# RefPoint01-00.net
KiCad netlist of a schematic drawn in Altium Designer
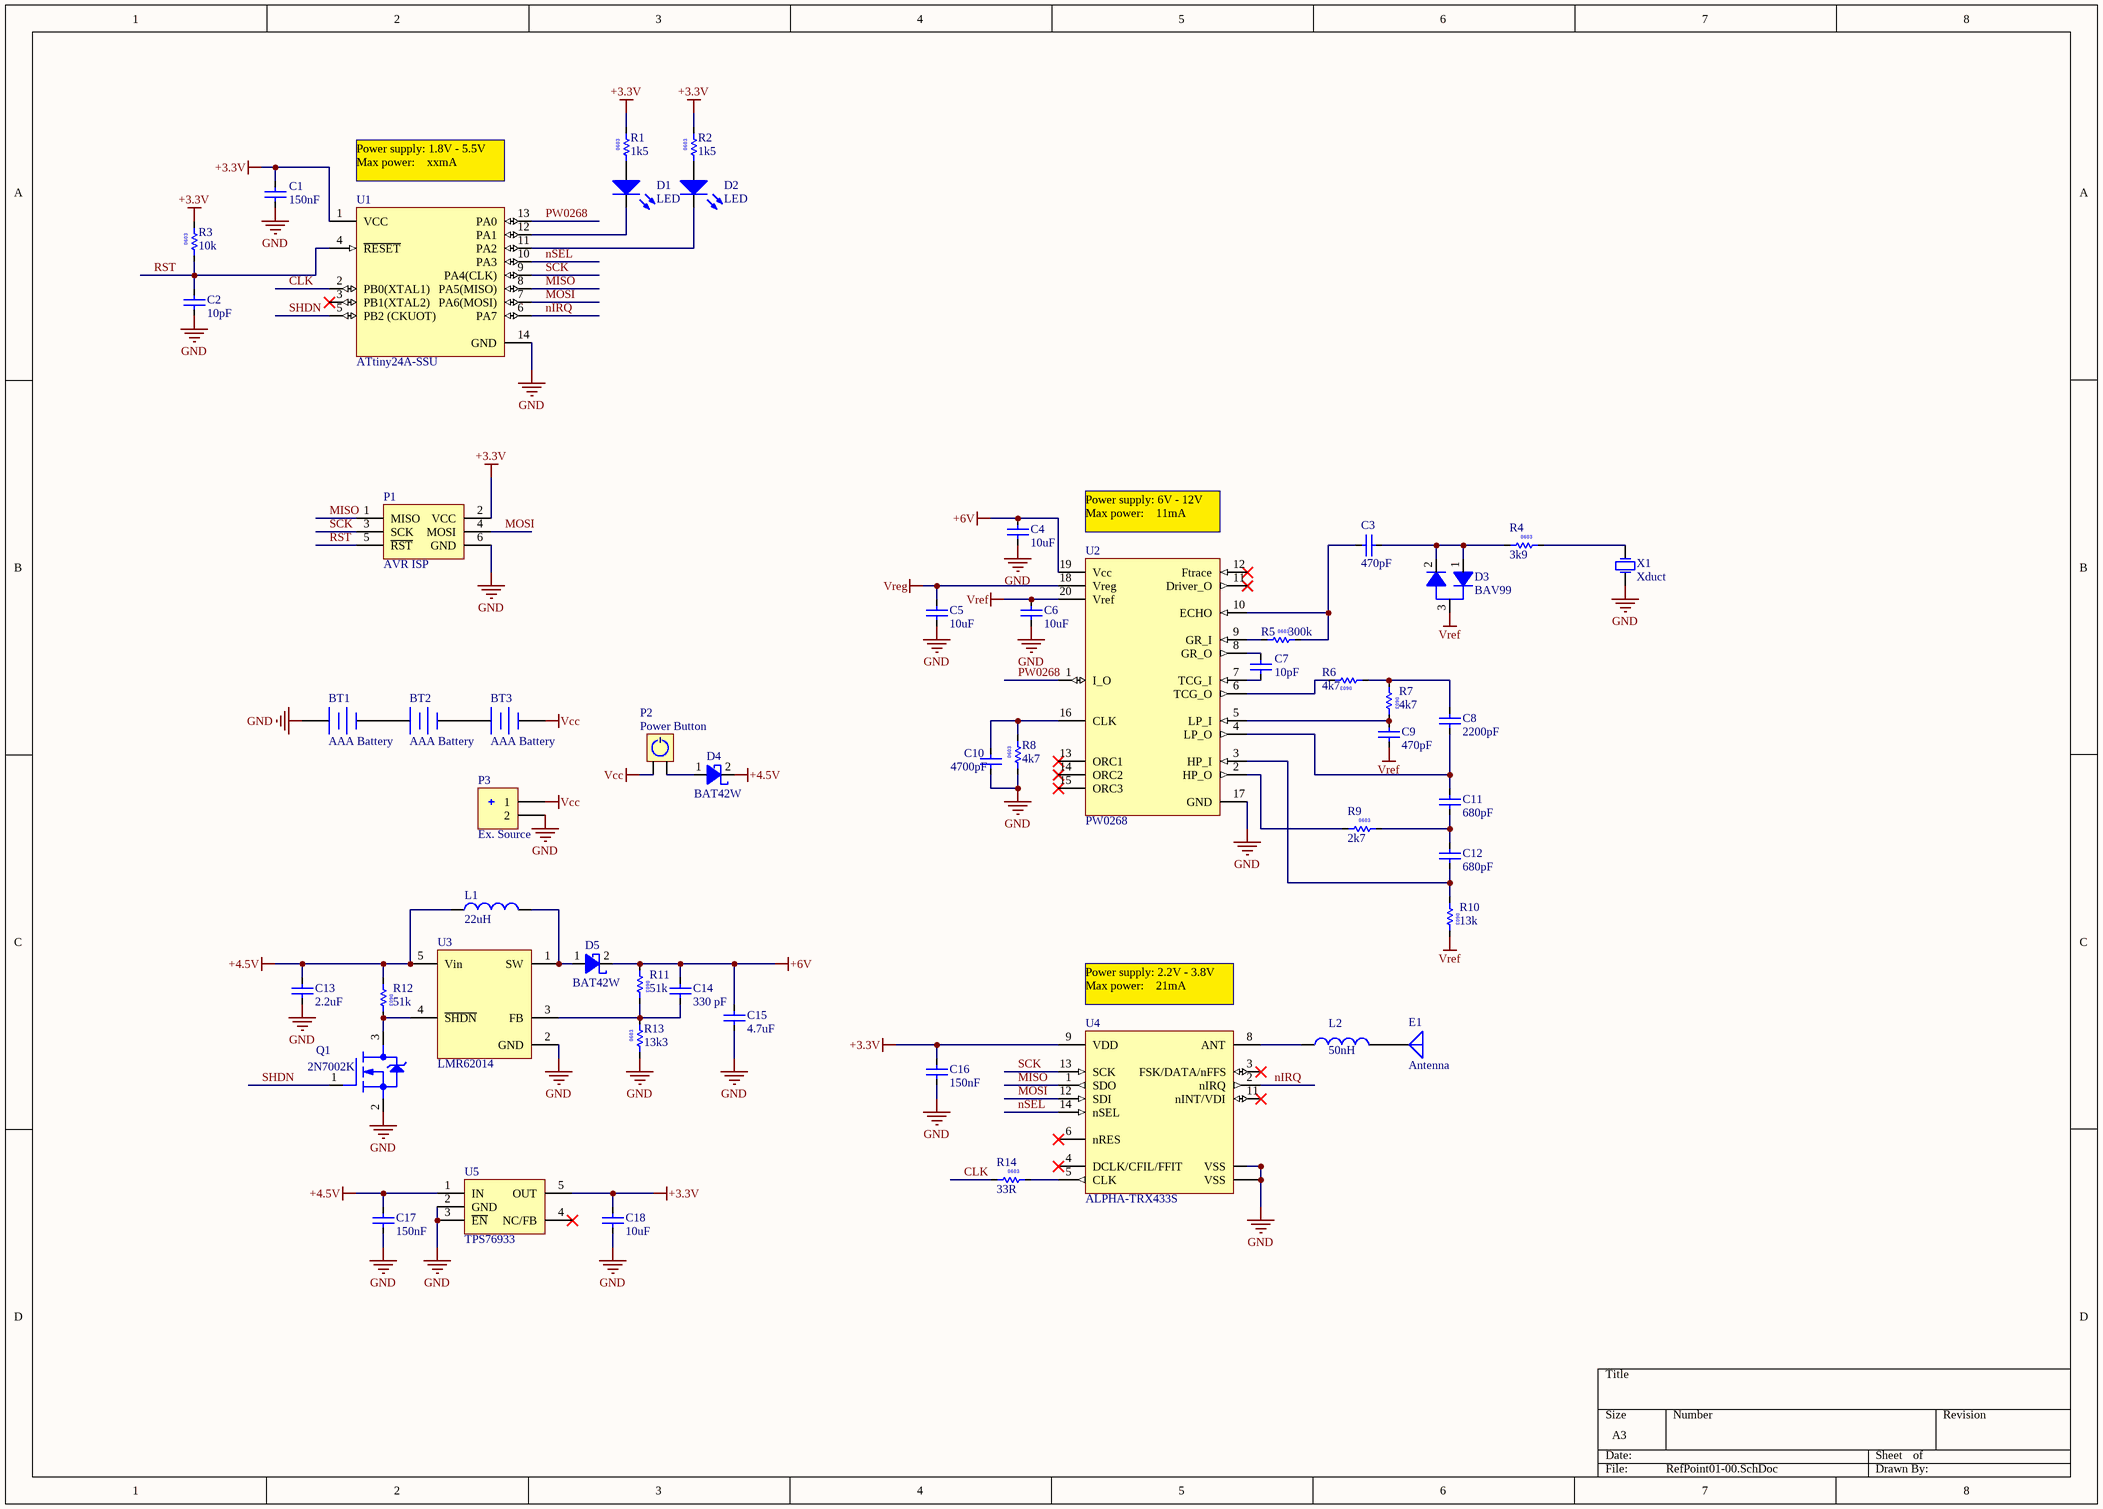
[diagram p0: RefPoint01-00.SchDoc]

(export (version "E")
  (design (tool "Eeschema 10.0.6"))
  (components
    (comp (ref "BT1")
      (value "AAA Battery")
      (footprint "Keystone 55 AAA CLIP")
      (description "Battery AAA")
      (fields (field (name "MANUFACTURER") "KEYSTONE") (field (name "MANUFACTURER PART NUMBER") "55"))
      (libsource (lib "UserSchlib") (part "Battery_AAA"))
    )
    (comp (ref "BT2")
      (value "AAA Battery")
      (footprint "Keystone 55 AAA CLIP")
      (description "Battery AAA")
      (fields (field (name "MANUFACTURER") "KEYSTONE") (field (name "MANUFACTURER PART NUMBER") "55"))
      (libsource (lib "UserSchlib") (part "Battery_AAA"))
    )
    (comp (ref "BT3")
      (value "AAA Battery")
      (footprint "Keystone 55 AAA CLIP")
      (description "Battery AAA")
      (fields (field (name "MANUFACTURER") "KEYSTONE") (field (name "MANUFACTURER PART NUMBER") "55"))
      (libsource (lib "UserSchlib") (part "Battery_AAA"))
    )
    (comp (ref "C1")
      (value "150nF")
      (footprint "CAPC1608N")
      (description "MLCC, 150nF 16V -20+80% Y5V")
      (fields (field (name "PART NUMBER") "C0000001") (field (name "VOLTAGE") "16"))
      (libsource (lib "KTU_DB") (part "C_SM"))
    )
    (comp (ref "C2")
      (value "10pF")
      (footprint "CAPC1608N")
      (description "MLCC, 0603, NP0, 50V, 10PF")
      (fields (field (name "PART NUMBER") "C0000042") (field (name "VOLTAGE") "100"))
      (libsource (lib "KTU_DB") (part "C_SM"))
    )
    (comp (ref "C3")
      (value "470pF")
      (footprint "CAPC1608N")
      (description "MLCC, 470pF 50V C0G 5% 0603")
      (fields (field (name "PART NUMBER") "C0000062") (field (name "VOLTAGE") "50"))
      (libsource (lib "KTU_DB") (part "C_SM"))
    )
    (comp (ref "C4")
      (value "10uF")
      (footprint "CAPC3216N")
      (description "MLCC, 10uF 25V -20%, +80% Y5V 1206")
      (fields (field (name "PART NUMBER") "C0000011") (field (name "VOLTAGE") "25"))
      (libsource (lib "KTU_DB") (part "C_SM"))
    )
    (comp (ref "C5")
      (value "10uF")
      (footprint "CAPC3216N")
      (description "MLCC, 10uF 25V -20%, +80% Y5V 1206")
      (fields (field (name "PART NUMBER") "C0000011") (field (name "VOLTAGE") "25"))
      (libsource (lib "KTU_DB") (part "C_SM"))
    )
    (comp (ref "C6")
      (value "10uF")
      (footprint "CAPC3216N")
      (description "MLCC, 10uF 25V -20%, +80% Y5V 1206")
      (fields (field (name "PART NUMBER") "C0000011") (field (name "VOLTAGE") "25"))
      (libsource (lib "KTU_DB") (part "C_SM"))
    )
    (comp (ref "C7")
      (value "10pF")
      (footprint "CAPC1608N")
      (description "MLCC, 0603, NP0, 50V, 10PF")
      (fields (field (name "PART NUMBER") "C0000042") (field (name "VOLTAGE") "100"))
      (libsource (lib "KTU_DB") (part "C_SM"))
    )
    (comp (ref "C8")
      (value "2200pF")
      (footprint "CAPC1608N")
      (description "MLCC, 2200pF 50V X7R 5% 0603")
      (fields (field (name "PART NUMBER") "C0000126") (field (name "VOLTAGE") "50"))
      (libsource (lib "KTU_DB") (part "C_SM"))
    )
    (comp (ref "C9")
      (value "470pF")
      (footprint "CAPC1608N")
      (description "MLCC, 470pF 50V C0G 5% 0603")
      (fields (field (name "PART NUMBER") "C0000062") (field (name "VOLTAGE") "50"))
      (libsource (lib "KTU_DB") (part "C_SM"))
    )
    (comp (ref "C10")
      (value "4700pF")
      (footprint "CAPC1608N")
      (description "MLCC, 4700pF 50V X7R 5% 0603")
      (fields (field (name "PART NUMBER") "C0000127") (field (name "VOLTAGE") "50"))
      (libsource (lib "KTU_DB") (part "C_SM"))
    )
    (comp (ref "C11")
      (value "680pF")
      (footprint "CAPC1608N")
      (description "MLCC, 680pF 50V C0G / NP0 5% 0603")
      (fields (field (name "PART NUMBER") "C0000125") (field (name "VOLTAGE") "50"))
      (libsource (lib "KTU_DB") (part "C_SM"))
    )
    (comp (ref "C12")
      (value "680pF")
      (footprint "CAPC1608N")
      (description "MLCC, 680pF 50V C0G / NP0 5% 0603")
      (fields (field (name "PART NUMBER") "C0000125") (field (name "VOLTAGE") "50"))
      (libsource (lib "KTU_DB") (part "C_SM"))
    )
    (comp (ref "C13")
      (value "2.2uF")
      (footprint "CAPC2012N")
      (description "MLCC, 2.2uF 16V X7R 0805")
      (fields (field (name "PART NUMBER") "C0000129") (field (name "VOLTAGE") "16V"))
      (libsource (lib "KTU_DB") (part "C_SM"))
    )
    (comp (ref "C14")
      (value "330 pF")
      (footprint "CAPC1608N")
      (description "MLCC, 50V, 330pF, 10%, X7R, 0603")
      (fields (field (name "PART NUMBER") "C0000018") (field (name "VOLTAGE") "50"))
      (libsource (lib "KTU_DB") (part "C_SM"))
    )
    (comp (ref "C15")
      (value "4.7uF")
      (footprint "CAPC3225N")
      (description "MLCC, 4.7uF 16V X7R 1210")
      (fields (field (name "PART NUMBER") "C0000130") (field (name "VOLTAGE") "50V"))
      (libsource (lib "KTU_DB") (part "C_SM"))
    )
    (comp (ref "C16")
      (value "150nF")
      (footprint "CAPC1608N")
      (description "MLCC, 150nF 16V -20+80% Y5V")
      (fields (field (name "PART NUMBER") "C0000001") (field (name "VOLTAGE") "16"))
      (libsource (lib "KTU_DB") (part "C_SM"))
    )
    (comp (ref "C17")
      (value "150nF")
      (footprint "CAPC1608N")
      (description "MLCC, 150nF 16V -20+80% Y5V")
      (fields (field (name "PART NUMBER") "C0000001") (field (name "VOLTAGE") "16"))
      (libsource (lib "KTU_DB") (part "C_SM"))
    )
    (comp (ref "C18")
      (value "10uF")
      (footprint "CAPC3216N")
      (description "MLCC, 10uF 25V -20%, +80% Y5V 1206")
      (fields (field (name "PART NUMBER") "C0000011") (field (name "VOLTAGE") "25"))
      (libsource (lib "KTU_DB") (part "C_SM"))
    )
    (comp (ref "D1")
      (value "LED")
      (footprint "LED 3mm DIP")
      (description "Typical INFRARED GaAs LED")
      (fields (field (name "PUBLISHER") "Altium Limited"))
      (libsource (lib "UserSchlib") (part "LED0"))
    )
    (comp (ref "D2")
      (value "LED")
      (footprint "LED 3mm DIP")
      (description "Typical INFRARED GaAs LED")
      (fields (field (name "PUBLISHER") "Altium Limited"))
      (libsource (lib "UserSchlib") (part "LED0"))
    )
    (comp (ref "D3")
      (value "BAV99")
      (footprint "SOT95P240-3L")
      (description "DIODE SW DUAL 75V 350mW SOT23")
      (fields (field (name "PART NUMBER") "D0000001") (field (name "MANUFACTURER") "ON SEMICONDUCTOR"))
      (libsource (lib "KTU_DB") (part "BAV99"))
    )
    (comp (ref "D4")
      (value "BAT42W")
      (footprint "SOD123")
      (description "Diode Schottkey, 30V, Vf=1V, If=1A, rrt=5ns, SOD123, -55°C to +125°C")
      (fields (field (name "PART NUMBER") "D0000003") (field (name "MANUFACTURER") "VISHAY SEMICONDUCTOR"))
      (libsource (lib "KTU_DB") (part "Diode_SCHOTTKY"))
    )
    (comp (ref "D5")
      (value "BAT42W")
      (footprint "SOD123")
      (description "Diode Schottkey, 30V, Vf=1V, If=1A, rrt=5ns, SOD123, -55°C to +125°C")
      (fields (field (name "PART NUMBER") "D0000003") (field (name "MANUFACTURER") "VISHAY SEMICONDUCTOR"))
      (libsource (lib "KTU_DB") (part "Diode_SCHOTTKY"))
    )
    (comp (ref "E1")
      (value "Antenna")
      (description "Generic Antenna")
      (fields (field (name "PUBLISHER") "Altium Limited"))
      (libsource (lib "Miscellaneous Devices") (part "Antenna"))
    )
    (comp (ref "L1")
      (value "22uH")
      (footprint "INDM7070x32N")
      (description "Inductor")
      (fields
        (field (name "MANUFACTURER PART NUMBER") "810-SLF732220MR962PF")
        (field (name "MANUFACTURER") "TDK")
      )
      (libsource (lib "UserSchlib") (part "L Inductor 810-SLF732220MR962PF"))
    )
    (comp (ref "L2")
      (value "50nH")
      (footprint "INDC2012L")
      (description "Inductor")
      (fields (field (name "PUBLISHER") "Altium Limited"))
      (libsource (lib "Miscellaneous Devices") (part "Inductor"))
    )
    (comp (ref "P1")
      (value "AVR ISP")
      (footprint "HDR2X3")
      (description "Header, 6-Pin")
      (fields (field (name "PUBLISHER") "Altium Limited"))
      (libsource (lib "Arthur Shematic") (part "AVR ISP"))
    )
    (comp (ref "P2")
      (value "Power Button")
      (footprint "HDR1X2")
      (description "Header, 2-Pin, Right Angle")
      (fields (field (name "PUBLISHER") "Altium Limited"))
      (libsource (lib "UserSchlib") (part "Power Button"))
    )
    (comp (ref "P3")
      (value "Ex. Source")
      (footprint "HDR1X2")
      (description "Header, 2-Pin")
      (fields (field (name "PUBLISHER") "Altium Limited"))
      (libsource (lib "Arthur Shematic") (part "Maitinimas"))
    )
    (comp (ref "Q1")
      (value "2N7002K")
      (footprint "SOT23-3L")
      (description "MOSFET N-CH 60V 340MA SOT23")
      (fields (field (name "PART NUMBER") "Q0000008") (field (name "MANUFACTURER") "NXP"))
      (libsource (lib "KTU_DB") (part "MOSFET_N_GSD"))
    )
    (comp (ref "R1")
      (value "1k5")
      (footprint "RESC1608N")
      (description "1K5 5% 0603 1/10W")
      (fields (field (name "TOLERANCE") "±5%") (field (name "POWER") "1/10W"))
      (libsource (lib "KTU_DB") (part "R0603"))
    )
    (comp (ref "R2")
      (value "1k5")
      (footprint "RESC1608N")
      (description "1K5 5% 0603 1/10W")
      (fields (field (name "TOLERANCE") "±5%") (field (name "POWER") "1/10W"))
      (libsource (lib "KTU_DB") (part "R0603"))
    )
    (comp (ref "R3")
      (value "10k")
      (footprint "RESC1608N")
      (description "Res, 10K 0.063W 75V 1%  0603")
      (fields (field (name "TOLERANCE") "±1%") (field (name "POWER") "0.063W"))
      (libsource (lib "KTU_DB") (part "R0603"))
    )
    (comp (ref "R4")
      (value "3k9")
      (footprint "RESC1608N")
      (description "3K9 5% 0603 1/10W")
      (fields (field (name "TOLERANCE") "±5%") (field (name "POWER") "1/10W"))
      (libsource (lib "KTU_DB") (part "R0603"))
    )
    (comp (ref "R5")
      (value "300k")
      (footprint "RESC1608N")
      (description "300K 5% 0603 1/10W")
      (fields (field (name "TOLERANCE") "±5%") (field (name "POWER") "1/10W"))
      (libsource (lib "KTU_DB") (part "R0603"))
    )
    (comp (ref "R6")
      (value "4k7")
      (footprint "RESC1608N")
      (description "Res, 4K7 5% 0603 1/10W")
      (fields (field (name "TOLERANCE") "±5%") (field (name "POWER") "1/10W"))
      (libsource (lib "KTU_DB") (part "R0603"))
    )
    (comp (ref "R7")
      (value "4k7")
      (footprint "RESC1608N")
      (description "Res, 4K7 5% 0603 1/10W")
      (fields (field (name "TOLERANCE") "±5%") (field (name "POWER") "1/10W"))
      (libsource (lib "KTU_DB") (part "R0603"))
    )
    (comp (ref "R8")
      (value "4k7")
      (footprint "RESC1608N")
      (description "Res, 4K7 5% 0603 1/10W")
      (fields (field (name "TOLERANCE") "±5%") (field (name "POWER") "1/10W"))
      (libsource (lib "KTU_DB") (part "R0603"))
    )
    (comp (ref "R9")
      (value "2k7")
      (footprint "RESC1608N")
      (description "2K7 5% 0603 1/10W")
      (fields (field (name "TOLERANCE") "±5%") (field (name "POWER") "1/10W"))
      (libsource (lib "KTU_DB") (part "R0603"))
    )
    (comp (ref "R10")
      (value "13k")
      (footprint "RESC1608N")
      (description "13K 5% 0603 1/10W")
      (fields (field (name "TOLERANCE") "±5%") (field (name "POWER") "1/10W"))
      (libsource (lib "KTU_DB") (part "R0603"))
    )
    (comp (ref "R11")
      (value "51k")
      (footprint "RESC1608X50N")
      (description "Res, 51K, 0603 (1608 metric), ±1%, 100mW, 75V")
      (fields (field (name "TOLERANCE") "±1%") (field (name "POWER") "100mW"))
      (libsource (lib "KTU_DB") (part "R0603"))
    )
    (comp (ref "R12")
      (value "51k")
      (footprint "RESC1608X50N")
      (description "Res, 51K, 0603 (1608 metric), ±1%, 100mW, 75V")
      (fields (field (name "TOLERANCE") "±1%") (field (name "POWER") "100mW"))
      (libsource (lib "KTU_DB") (part "R0603"))
    )
    (comp (ref "R13")
      (value "13k3")
      (footprint "RESC1608X50N")
      (description "Res, 13K3, 0603 (1608 metric), ±1%, 100mW, 75V")
      (fields (field (name "TOLERANCE") "±1%") (field (name "POWER") "100mW"))
      (libsource (lib "KTU_DB") (part "R0603"))
    )
    (comp (ref "R14")
      (value "33R")
      (footprint "RESC1608N")
      (description "33R 5% 0603 1/10W")
      (fields (field (name "TOLERANCE") "±5%") (field (name "POWER") "1/10W"))
      (libsource (lib "KTU_DB") (part "R0603"))
    )
    (comp (ref "U1")
      (value "ATtiny24A-SSU")
      (footprint "UserPcbLib:SOIC14T_L")
      (fields (field (name "MANUFACTURER") "Atmel"))
      (libsource (lib "UserSchlib") (part "ATtiny24A-SSU"))
    )
    (comp (ref "U2")
      (value "PW0268")
      (footprint "QSSOP20_0.635/4.0X8.7")
      (fields (field (name "MANUFACTURER") "PROWAVE"))
      (libsource (lib "UserSchlib") (part "PW0268"))
    )
    (comp (ref "U3")
      (value "LMR62014")
      (footprint "SOT23-5AM")
      (description "2064695")
      (fields
        (field (name "MANUFACTURER PART NUMBER") "LMR62014XMFE")
        (field (name "MANUFACTURER") "TEXAS INSTRUMENTS")
      )
      (libsource (lib "UserSchlib") (part "LMR62014"))
    )
    (comp (ref "U4")
      (value "ALPHA-TRX433S")
      (footprint "ALPHA-TRX")
      (description "RF SOLUTIONS  ALPHA-TRX433S  RF MODULE, TRANSCEIVER, FSK, 433MHZ")
      (fields (field (name "MANUFACTURER") "RF SOLUTIONS"))
      (libsource (lib "UserSchlib") (part "ALPHA-TRX433S"))
    )
    (comp (ref "U5")
      (value "TPS76933")
      (footprint "SOT23-5AM")
      (description "ULTRALOW-POWER 100-mA LOW-DROPOUT LINEAR REGULATORS")
      (fields
        (field (name "MANUFACTURER PART NUMBER") "TPS76933DBVT")
        (field (name "MANUFACTURER") "TEXAS INSTRUMENTS")
      )
      (libsource (lib "UserSchlib") (part "TPS769xx"))
    )
    (comp (ref "X1")
      (value "Xduct")
      (footprint "Xducts1")
      (description "Transducer")
      (libsource (lib "UserSchlib") (part "Xduct1"))
    )
  )
  (nets
    (net (code "1") (name "+3.3V") (class "Default")
      (node (ref "C1") (pin "2") (pinfunction "2_2") (pintype "passive"))
      (node (ref "C16") (pin "2") (pinfunction "2_2") (pintype "passive"))
      (node (ref "C18") (pin "2") (pinfunction "2_2") (pintype "passive"))
      (node (ref "P1") (pin "2") (pinfunction "VCC_2") (pintype "passive"))
      (node (ref "R1") (pin "2") (pinfunction "2_2") (pintype "passive"))
      (node (ref "R2") (pin "2") (pinfunction "2_2") (pintype "passive"))
      (node (ref "R3") (pin "2") (pinfunction "2_2") (pintype "passive"))
      (node (ref "U1") (pin "1") (pinfunction "VCC_1") (pintype "power_in"))
      (node (ref "U4") (pin "9") (pinfunction "VDD_9") (pintype "power_in"))
      (node (ref "U5") (pin "5") (pinfunction "OUT_5") (pintype "power_in"))
    )
    (net (code "2") (name "+4.5V") (class "Default")
      (node (ref "C13") (pin "2") (pinfunction "2_2") (pintype "passive"))
      (node (ref "C17") (pin "2") (pinfunction "2_2") (pintype "passive"))
      (node (ref "D4") (pin "2") (pinfunction "CATHODE_2") (pintype "passive"))
      (node (ref "L1") (pin "2") (pinfunction "2_2") (pintype "passive"))
      (node (ref "R12") (pin "1") (pinfunction "1_1") (pintype "passive"))
      (node (ref "U3") (pin "5") (pinfunction "Vin_5") (pintype "passive"))
      (node (ref "U5") (pin "1") (pinfunction "IN_1") (pintype "power_in"))
    )
    (net (code "3") (name "+6V") (class "Default")
      (node (ref "C14") (pin "2") (pinfunction "2_2") (pintype "passive"))
      (node (ref "C15") (pin "2") (pinfunction "2_2") (pintype "passive"))
      (node (ref "C4") (pin "2") (pinfunction "2_2") (pintype "passive"))
      (node (ref "D5") (pin "2") (pinfunction "CATHODE_2") (pintype "passive"))
      (node (ref "R11") (pin "1") (pinfunction "1_1") (pintype "passive"))
      (node (ref "U2") (pin "19") (pinfunction "Vcc_19") (pintype "power_in"))
    )
    (net (code "4") (name "/CLK") (class "Default")
      (node (ref "R14") (pin "1") (pinfunction "1_1") (pintype "passive"))
      (node (ref "U1") (pin "2") (pinfunction "PB0(XTAL1)_2") (pintype "bidirectional"))
    )
    (net (code "5") (name "/MISO") (class "Default")
      (node (ref "P1") (pin "1") (pinfunction "MISO_1") (pintype "passive"))
      (node (ref "U1") (pin "8") (pinfunction "PA5(MISO)_8") (pintype "bidirectional"))
      (node (ref "U4") (pin "1") (pinfunction "SDO_1") (pintype "output"))
    )
    (net (code "6") (name "/MOSI") (class "Default")
      (node (ref "P1") (pin "4") (pinfunction "MOSI_4") (pintype "passive"))
      (node (ref "U1") (pin "7") (pinfunction "PA6(MOSI)_7") (pintype "bidirectional"))
      (node (ref "U4") (pin "12") (pinfunction "SDI_12") (pintype "input"))
    )
    (net (code "7") (name "/PW0268") (class "Default")
      (node (ref "U1") (pin "13") (pinfunction "PA0_13") (pintype "bidirectional"))
      (node (ref "U2") (pin "1") (pinfunction "I_O_1") (pintype "bidirectional"))
    )
    (net (code "8") (name "/RST") (class "Default")
      (node (ref "C2") (pin "2") (pinfunction "2_2") (pintype "passive"))
      (node (ref "P1") (pin "5") (pinfunction "~{RST}_5") (pintype "passive"))
      (node (ref "R3") (pin "1") (pinfunction "1_1") (pintype "passive"))
      (node (ref "U1") (pin "4") (pinfunction "~{RESET}_4") (pintype "input"))
    )
    (net (code "9") (name "/SCK") (class "Default")
      (node (ref "P1") (pin "3") (pinfunction "SCK_3") (pintype "passive"))
      (node (ref "U1") (pin "9") (pinfunction "PA4(CLK)_9") (pintype "bidirectional"))
      (node (ref "U4") (pin "13") (pinfunction "SCK_13") (pintype "input"))
    )
    (net (code "10") (name "/SHDN") (class "Default")
      (node (ref "Q1") (pin "1") (pinfunction "G_1") (pintype "passive"))
      (node (ref "U1") (pin "5") (pinfunction "PB2_(CKUOT)_5") (pintype "bidirectional"))
    )
    (net (code "11") (name "/nIRQ") (class "Default")
      (node (ref "U1") (pin "6") (pinfunction "PA7_6") (pintype "bidirectional"))
      (node (ref "U4") (pin "2") (pinfunction "nIRQ_2") (pintype "output"))
    )
    (net (code "12") (name "/nSEL") (class "Default")
      (node (ref "U1") (pin "10") (pinfunction "PA3_10") (pintype "bidirectional"))
      (node (ref "U4") (pin "14") (pinfunction "nSEL_14") (pintype "input"))
    )
    (net (code "13") (name "GND") (class "Default")
      (node (ref "BT1") (pin "1") (pinfunction "+_1") (pintype "passive"))
      (node (ref "C1") (pin "1") (pinfunction "1_1") (pintype "passive"))
      (node (ref "C10") (pin "1") (pinfunction "1_1") (pintype "passive"))
      (node (ref "C13") (pin "1") (pinfunction "1_1") (pintype "passive"))
      (node (ref "C15") (pin "1") (pinfunction "1_1") (pintype "passive"))
      (node (ref "C16") (pin "1") (pinfunction "1_1") (pintype "passive"))
      (node (ref "C17") (pin "1") (pinfunction "1_1") (pintype "passive"))
      (node (ref "C18") (pin "1") (pinfunction "1_1") (pintype "passive"))
      (node (ref "C2") (pin "1") (pinfunction "1_1") (pintype "passive"))
      (node (ref "C4") (pin "1") (pinfunction "1_1") (pintype "passive"))
      (node (ref "C5") (pin "1") (pinfunction "1_1") (pintype "passive"))
      (node (ref "C6") (pin "1") (pinfunction "1_1") (pintype "passive"))
      (node (ref "P1") (pin "6") (pinfunction "GND_6") (pintype "passive"))
      (node (ref "P3") (pin "2") (pinfunction "2_2") (pintype "passive"))
      (node (ref "Q1") (pin "2") (pinfunction "S_2") (pintype "passive"))
      (node (ref "R13") (pin "1") (pinfunction "1_1") (pintype "passive"))
      (node (ref "R8") (pin "1") (pinfunction "1_1") (pintype "passive"))
      (node (ref "U1") (pin "14") (pinfunction "GND_14") (pintype "power_in"))
      (node (ref "U2") (pin "17") (pinfunction "GND_17") (pintype "power_in"))
      (node (ref "U3") (pin "2") (pinfunction "GND_2") (pintype "passive"))
      (node (ref "U4") (pin "10") (pinfunction "VSS_10") (pintype "power_in"))
      (node (ref "U4") (pin "7") (pinfunction "VSS_7") (pintype "power_in"))
      (node (ref "U5") (pin "2") (pinfunction "GND_2") (pintype "power_in"))
      (node (ref "U5") (pin "3") (pinfunction "~{EN}_3") (pintype "power_in"))
      (node (ref "X1") (pin "2") (pinfunction "2_2") (pintype "passive"))
    )
    (net (code "14") (name "Net-(BT1--)") (class "Default")
      (node (ref "BT1") (pin "2") (pinfunction "-_2") (pintype "passive"))
      (node (ref "BT2") (pin "1") (pinfunction "+_1") (pintype "passive"))
    )
    (net (code "15") (name "Net-(BT2--)") (class "Default")
      (node (ref "BT2") (pin "2") (pinfunction "-_2") (pintype "passive"))
      (node (ref "BT3") (pin "1") (pinfunction "+_1") (pintype "passive"))
    )
    (net (code "16") (name "Net-(C8-Pad2)") (class "Default")
      (node (ref "C8") (pin "2") (pinfunction "2_2") (pintype "passive"))
      (node (ref "R6") (pin "1") (pinfunction "1_1") (pintype "passive"))
      (node (ref "R7") (pin "1") (pinfunction "1_1") (pintype "passive"))
    )
    (net (code "17") (name "Net-(C11-Pad2)") (class "Default")
      (node (ref "C11") (pin "2") (pinfunction "2_2") (pintype "passive"))
      (node (ref "C12") (pin "1") (pinfunction "1_1") (pintype "passive"))
      (node (ref "R9") (pin "2") (pinfunction "2_2") (pintype "passive"))
    )
    (net (code "18") (name "Net-(D1-A)") (class "Default")
      (node (ref "D1") (pin "1") (pinfunction "A_1") (pintype "passive"))
      (node (ref "R1") (pin "1") (pinfunction "1_1") (pintype "passive"))
    )
    (net (code "19") (name "Net-(D1-K)") (class "Default")
      (node (ref "D1") (pin "2") (pinfunction "K_2") (pintype "passive"))
      (node (ref "U1") (pin "12") (pinfunction "PA1_12") (pintype "bidirectional"))
    )
    (net (code "20") (name "Net-(D2-A)") (class "Default")
      (node (ref "D2") (pin "1") (pinfunction "A_1") (pintype "passive"))
      (node (ref "R2") (pin "1") (pinfunction "1_1") (pintype "passive"))
    )
    (net (code "21") (name "Net-(D2-K)") (class "Default")
      (node (ref "D2") (pin "2") (pinfunction "K_2") (pintype "passive"))
      (node (ref "U1") (pin "11") (pinfunction "PA2_11") (pintype "bidirectional"))
    )
    (net (code "22") (name "Net-(D3-A)") (class "Default")
      (node (ref "C3") (pin "2") (pinfunction "2_2") (pintype "passive"))
      (node (ref "D3") (pin "1") (pinfunction "A1_1") (pintype "passive"))
      (node (ref "D3") (pin "2") (pinfunction "A_2") (pintype "passive"))
      (node (ref "R4") (pin "1") (pinfunction "1_1") (pintype "passive"))
    )
    (net (code "23") (name "Net-(D4-ANODE)") (class "Default")
      (node (ref "D4") (pin "1") (pinfunction "ANODE_1") (pintype "passive"))
      (node (ref "P2") (pin "2") (pinfunction "2_2") (pintype "passive"))
    )
    (net (code "24") (name "Net-(D5-ANODE)") (class "Default")
      (node (ref "D5") (pin "1") (pinfunction "ANODE_1") (pintype "passive"))
      (node (ref "L1") (pin "1") (pinfunction "1_1") (pintype "passive"))
      (node (ref "U3") (pin "1") (pinfunction "SW_1") (pintype "passive"))
    )
    (net (code "25") (name "Net-(E1-A)") (class "Default")
      (node (ref "E1") (pin "1") (pinfunction "A_1") (pintype "passive"))
      (node (ref "L2") (pin "2") (pinfunction "2_2") (pintype "passive"))
    )
    (net (code "26") (name "Net-(Q1-D)") (class "Default")
      (node (ref "Q1") (pin "3") (pinfunction "D_3") (pintype "passive"))
      (node (ref "R12") (pin "2") (pinfunction "2_2") (pintype "passive"))
      (node (ref "U3") (pin "4") (pinfunction "~{SHDN}_4") (pintype "passive"))
    )
    (net (code "27") (name "Net-(R4-Pad2)") (class "Default")
      (node (ref "R4") (pin "2") (pinfunction "2_2") (pintype "passive"))
      (node (ref "X1") (pin "1") (pinfunction "1_1") (pintype "passive"))
    )
    (net (code "28") (name "Net-(U2-CLK)") (class "Default")
      (node (ref "C10") (pin "2") (pinfunction "2_2") (pintype "passive"))
      (node (ref "R8") (pin "2") (pinfunction "2_2") (pintype "passive"))
      (node (ref "U2") (pin "16") (pinfunction "CLK_16") (pintype "passive"))
    )
    (net (code "29") (name "Net-(U2-ECHO)") (class "Default")
      (node (ref "C3") (pin "1") (pinfunction "1_1") (pintype "passive"))
      (node (ref "R5") (pin "2") (pinfunction "2_2") (pintype "passive"))
      (node (ref "U2") (pin "10") (pinfunction "ECHO_10") (pintype "input"))
    )
    (net (code "30") (name "Net-(U2-GR_I)") (class "Default")
      (node (ref "R5") (pin "1") (pinfunction "1_1") (pintype "passive"))
      (node (ref "U2") (pin "9") (pinfunction "GR_I_9") (pintype "input"))
    )
    (net (code "31") (name "Net-(U2-GR_O)") (class "Default")
      (node (ref "C7") (pin "1") (pinfunction "1_1") (pintype "passive"))
      (node (ref "U2") (pin "8") (pinfunction "GR_O_8") (pintype "output"))
    )
    (net (code "32") (name "Net-(U2-HP_I)") (class "Default")
      (node (ref "C12") (pin "2") (pinfunction "2_2") (pintype "passive"))
      (node (ref "R10") (pin "1") (pinfunction "1_1") (pintype "passive"))
      (node (ref "U2") (pin "3") (pinfunction "HP_I_3") (pintype "input"))
    )
    (net (code "33") (name "Net-(U2-HP_O)") (class "Default")
      (node (ref "R9") (pin "1") (pinfunction "1_1") (pintype "passive"))
      (node (ref "U2") (pin "2") (pinfunction "HP_O_2") (pintype "output"))
    )
    (net (code "34") (name "Net-(U2-LP_I)") (class "Default")
      (node (ref "C9") (pin "2") (pinfunction "2_2") (pintype "passive"))
      (node (ref "R7") (pin "2") (pinfunction "2_2") (pintype "passive"))
      (node (ref "U2") (pin "5") (pinfunction "LP_I_5") (pintype "input"))
    )
    (net (code "35") (name "Net-(U2-LP_O)") (class "Default")
      (node (ref "C11") (pin "1") (pinfunction "1_1") (pintype "passive"))
      (node (ref "C8") (pin "1") (pinfunction "1_1") (pintype "passive"))
      (node (ref "U2") (pin "4") (pinfunction "LP_O_4") (pintype "output"))
    )
    (net (code "36") (name "Net-(U2-TCG_I)") (class "Default")
      (node (ref "C7") (pin "2") (pinfunction "2_2") (pintype "passive"))
      (node (ref "U2") (pin "7") (pinfunction "TCG_I_7") (pintype "input"))
    )
    (net (code "37") (name "Net-(U2-TCG_O)") (class "Default")
      (node (ref "R6") (pin "2") (pinfunction "2_2") (pintype "passive"))
      (node (ref "U2") (pin "6") (pinfunction "TCG_O_6") (pintype "output"))
    )
    (net (code "38") (name "Net-(U3-FB)") (class "Default")
      (node (ref "C14") (pin "1") (pinfunction "1_1") (pintype "passive"))
      (node (ref "R11") (pin "2") (pinfunction "2_2") (pintype "passive"))
      (node (ref "R13") (pin "2") (pinfunction "2_2") (pintype "passive"))
      (node (ref "U3") (pin "3") (pinfunction "FB_3") (pintype "passive"))
    )
    (net (code "39") (name "Net-(U4-ANT)") (class "Default")
      (node (ref "L2") (pin "1") (pinfunction "1_1") (pintype "passive"))
      (node (ref "U4") (pin "8") (pinfunction "ANT_8") (pintype "passive"))
    )
    (net (code "40") (name "Net-(U4-CLK)") (class "Default")
      (node (ref "R14") (pin "2") (pinfunction "2_2") (pintype "passive"))
      (node (ref "U4") (pin "5") (pinfunction "CLK_5") (pintype "output"))
    )
    (net (code "41") (name "Vcc") (class "Default")
      (node (ref "BT3") (pin "2") (pinfunction "-_2") (pintype "passive"))
      (node (ref "P2") (pin "1") (pinfunction "1_1") (pintype "passive"))
      (node (ref "P3") (pin "1") (pinfunction "1_1") (pintype "passive"))
    )
    (net (code "42") (name "Vref") (class "Default")
      (node (ref "C6") (pin "2") (pinfunction "2_2") (pintype "passive"))
      (node (ref "C9") (pin "1") (pinfunction "1_1") (pintype "passive"))
      (node (ref "D3") (pin "3") (pinfunction "K_3") (pintype "passive"))
      (node (ref "R10") (pin "2") (pinfunction "2_2") (pintype "passive"))
      (node (ref "U2") (pin "20") (pinfunction "Vref_20") (pintype "power_in"))
    )
    (net (code "43") (name "Vreg") (class "Default")
      (node (ref "C5") (pin "2") (pinfunction "2_2") (pintype "passive"))
      (node (ref "U2") (pin "18") (pinfunction "Vreg_18") (pintype "power_in"))
    )
    (net (code "44") (name "unconnected-(U1-PB1(XTAL2)-Pad3)") (class "Default")
      (node (ref "U1") (pin "3") (pinfunction "PB1(XTAL2)_3") (pintype "bidirectional+no_connect"))
    )
    (net (code "45") (name "unconnected-(U2-Driver_O-Pad11)") (class "Default")
      (node (ref "U2") (pin "11") (pinfunction "Driver_O_11") (pintype "output+no_connect"))
    )
    (net (code "46") (name "unconnected-(U2-Ftrace-Pad12)") (class "Default")
      (node (ref "U2") (pin "12") (pinfunction "Ftrace_12") (pintype "input+no_connect"))
    )
    (net (code "47") (name "unconnected-(U2-ORC1-Pad13)") (class "Default")
      (node (ref "U2") (pin "13") (pinfunction "ORC1_13") (pintype "passive+no_connect"))
    )
    (net (code "48") (name "unconnected-(U2-ORC2-Pad14)") (class "Default")
      (node (ref "U2") (pin "14") (pinfunction "ORC2_14") (pintype "passive+no_connect"))
    )
    (net (code "49") (name "unconnected-(U2-ORC3-Pad15)") (class "Default")
      (node (ref "U2") (pin "15") (pinfunction "ORC3_15") (pintype "passive+no_connect"))
    )
    (net (code "50") (name "unconnected-(U4-DCLK{slash}CFIL{slash}FFIT-Pad4)") (class "Default")
      (node (ref "U4") (pin "4") (pinfunction "DCLK/CFIL/FFIT_4") (pintype "passive+no_connect"))
    )
    (net (code "51") (name "unconnected-(U4-FSK{slash}DATA{slash}nFFS-Pad3)") (class "Default")
      (node (ref "U4") (pin "3") (pinfunction "FSK/DATA/nFFS_3") (pintype "bidirectional+no_connect"))
    )
    (net (code "52") (name "unconnected-(U4-nINT{slash}VDI-Pad11)") (class "Default")
      (node (ref "U4") (pin "11") (pinfunction "nINT/VDI_11") (pintype "bidirectional+no_connect"))
    )
    (net (code "53") (name "unconnected-(U4-nRES-Pad6)") (class "Default")
      (node (ref "U4") (pin "6") (pinfunction "nRES_6") (pintype "passive+no_connect"))
    )
    (net (code "54") (name "unconnected-(U5-NC{slash}FB-Pad4)") (class "Default")
      (node (ref "U5") (pin "4") (pinfunction "NC/FB_4") (pintype "power_in+no_connect"))
    )
  )
)
